# BMI270-Accelerometer-Gyroscope.net
KiCad netlist of a schematic drawn in Altium Designer
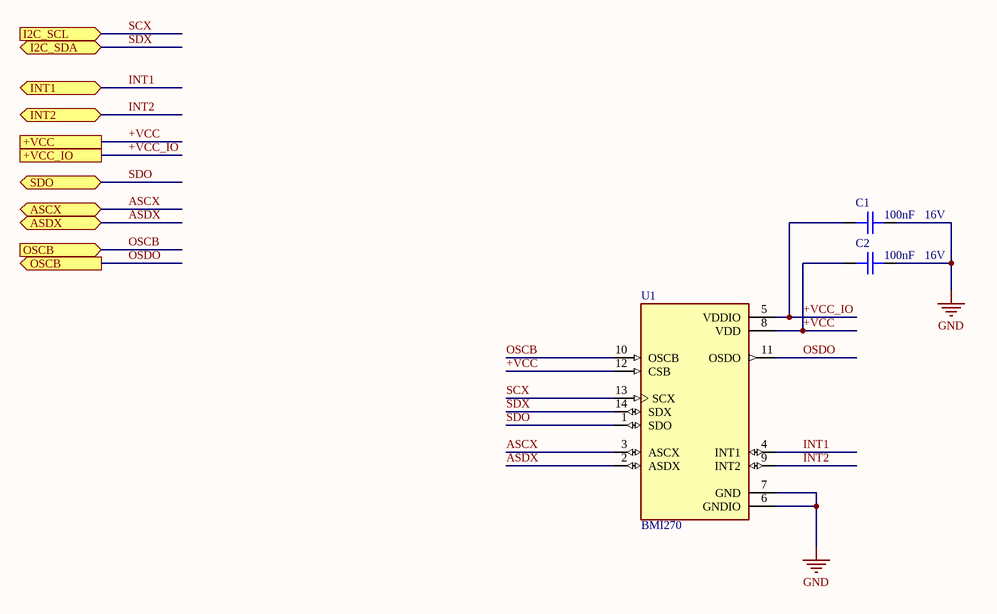
[diagram p0: BMI270-Accelerometer-Gyroscope.SchDoc]

(export (version "E")
  (design (tool "Eeschema 10.0.6"))
  (components
    (comp (ref "C1")
      (value "CAP CER 0.1UF 16V X7R 0402")
      (footprint "C0402")
      (description "0.1µF ±10% 16V Ceramic Capacitor X7R 0402 (1005 Metric)")
      (fields
        (field (name "MANUFACTURER PART NUMBER") "CC0402KRX7R7BB104")
        (field (name "MANUFACTURER") "Yageo")
        (field (name "CAPACITANCE") "100nF")
        (field (name "VOLTAGE") "16V")
      )
      (libsource (lib "Control_Board_Model_C201") (part "CAP CER 0.1UF 16V X7R 0402"))
    )
    (comp (ref "C2")
      (value "CAP CER 0.1UF 16V X7R 0402")
      (footprint "C0402")
      (description "0.1µF ±10% 16V Ceramic Capacitor X7R 0402 (1005 Metric)")
      (fields
        (field (name "MANUFACTURER PART NUMBER") "CC0402KRX7R7BB104")
        (field (name "MANUFACTURER") "Yageo")
        (field (name "CAPACITANCE") "100nF")
        (field (name "VOLTAGE") "16V")
      )
      (libsource (lib "Control_Board_Model_C201") (part "CAP CER 0.1UF 16V X7R 0402"))
    )
    (comp (ref "U1")
      (value "BMI270")
      (footprint "XDCR_BMI270")
      (description "Accelerometer, Gyroscope, 6 Axis Sensor IÂ²C, SPI Output")
      (fields (field (name "MF") "Bosch Sensortec"))
      (libsource (lib "BMI270") (part "BMI270"))
    )
  )
  (nets
    (net (code "1") (name "/+VCC") (class "Default")
      (node (ref "C1") (pin "1") (pinfunction "1_1") (pintype "passive"))
      (node (ref "C2") (pin "1") (pinfunction "1_1") (pintype "passive"))
      (node (ref "U1") (pin "12") (pinfunction "CSB_12") (pintype "input"))
      (node (ref "U1") (pin "5") (pinfunction "VDDIO_5") (pintype "power_in"))
      (node (ref "U1") (pin "8") (pinfunction "VDD_8") (pintype "power_in"))
    )
    (net (code "2") (name "/ASCX") (class "Default")
      (node (ref "U1") (pin "3") (pinfunction "ASCX_3") (pintype "bidirectional"))
    )
    (net (code "3") (name "/ASDX") (class "Default")
      (node (ref "U1") (pin "2") (pinfunction "ASDX_2") (pintype "bidirectional"))
    )
    (net (code "4") (name "/INT1") (class "Default")
      (node (ref "U1") (pin "4") (pinfunction "INT1_4") (pintype "bidirectional"))
    )
    (net (code "5") (name "/INT2") (class "Default")
      (node (ref "U1") (pin "9") (pinfunction "INT2_9") (pintype "bidirectional"))
    )
    (net (code "6") (name "/OSCB") (class "Default")
      (node (ref "U1") (pin "10") (pinfunction "OSCB_10") (pintype "input"))
      (node (ref "U1") (pin "11") (pinfunction "OSDO_11") (pintype "output"))
    )
    (net (code "7") (name "/SCX") (class "Default")
      (node (ref "U1") (pin "13") (pinfunction "SCX_13") (pintype "input"))
    )
    (net (code "8") (name "/SDO") (class "Default")
      (node (ref "U1") (pin "1") (pinfunction "SDO_1") (pintype "bidirectional"))
    )
    (net (code "9") (name "/SDX") (class "Default")
      (node (ref "U1") (pin "14") (pinfunction "SDX_14") (pintype "bidirectional"))
    )
    (net (code "10") (name "GND") (class "Default")
      (node (ref "C1") (pin "2") (pinfunction "2_2") (pintype "passive"))
      (node (ref "C2") (pin "2") (pinfunction "2_2") (pintype "passive"))
      (node (ref "U1") (pin "6") (pinfunction "GNDIO_6") (pintype "power_in"))
      (node (ref "U1") (pin "7") (pinfunction "GND_7") (pintype "power_in"))
    )
  )
)
